# AND_opertaions.net
KiCad netlist of a schematic drawn in Altium Designer
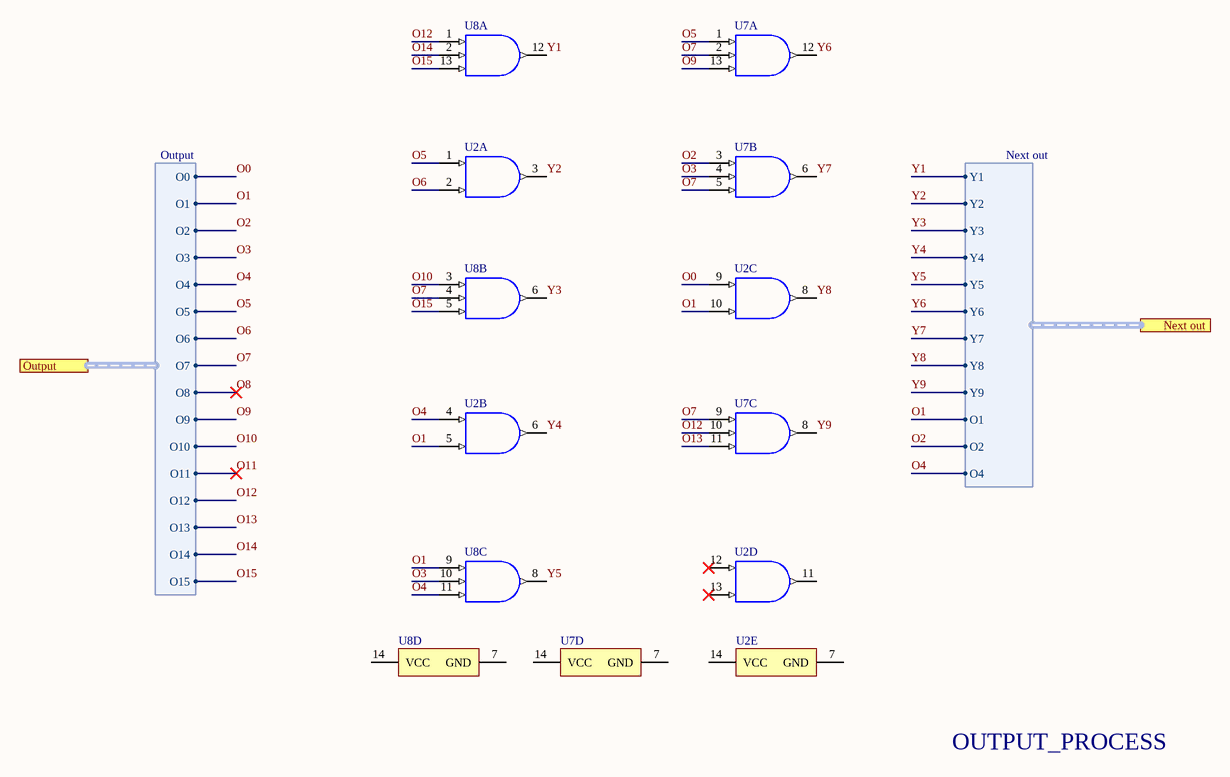
[diagram p0: AND_opertaions.SchDoc]

(export (version "E")
  (design (tool "Eeschema 10.0.6"))
  (components
    (comp (ref "U2")
      (value "SN74S08N")
      (footprint "N0014A")
      (description "Quad 2-input positive-AND gates, N0014A, TUBE")
      (fields
        (field (name "MANUFACTURER") "Texas Instruments")
        (field (name "GENERIC PART NUMBER") "SN74S08")
      )
      (libsource (lib "Altium Content Vault") (part "TI-AND-4-2IN-14"))
    )
    (comp (ref "U7")
      (value "SN74LS11N")
      (footprint "N0014A")
      (description "Triple 3-input positive-AND gates, N0014A, TUBE")
      (fields
        (field (name "MANUFACTURER") "Texas Instruments")
        (field (name "GENERIC PART NUMBER") "SN74LS11")
      )
      (libsource (lib "Altium Content Vault") (part "TI-AND-3-3IN-14"))
    )
    (comp (ref "U8")
      (value "SN74LS11N")
      (footprint "N0014A")
      (description "Triple 3-input positive-AND gates, N0014A, TUBE")
      (fields
        (field (name "MANUFACTURER") "Texas Instruments")
        (field (name "GENERIC PART NUMBER") "SN74LS11")
      )
      (libsource (lib "Altium Content Vault") (part "TI-AND-3-3IN-14"))
    )
  )
  (nets
    (net (code "4") (name "/O0") (class "Default")
      (node (ref "U2") (pin "9") (pinfunction "3A_9") (pintype "input"))
    )
    (net (code "5") (name "/O1") (class "Default")
      (node (ref "U2") (pin "10") (pinfunction "3B_10") (pintype "input"))
      (node (ref "U2") (pin "5") (pinfunction "2B_5") (pintype "input"))
      (node (ref "U8") (pin "9") (pinfunction "3A_9") (pintype "input"))
    )
    (net (code "6") (name "/O2") (class "Default")
      (node (ref "U7") (pin "3") (pinfunction "2A_3") (pintype "input"))
    )
    (net (code "7") (name "/O3") (class "Default")
      (node (ref "U7") (pin "4") (pinfunction "2B_4") (pintype "input"))
      (node (ref "U8") (pin "10") (pinfunction "3B_10") (pintype "input"))
    )
    (net (code "8") (name "/O4") (class "Default")
      (node (ref "U2") (pin "4") (pinfunction "2A_4") (pintype "input"))
      (node (ref "U8") (pin "11") (pinfunction "3C_11") (pintype "input"))
    )
    (net (code "9") (name "/O5") (class "Default")
      (node (ref "U2") (pin "1") (pinfunction "1A_1") (pintype "input"))
      (node (ref "U7") (pin "1") (pinfunction "1A_1") (pintype "input"))
    )
    (net (code "10") (name "/O6") (class "Default")
      (node (ref "U2") (pin "2") (pinfunction "1B_2") (pintype "input"))
    )
    (net (code "11") (name "/O7") (class "Default")
      (node (ref "U7") (pin "2") (pinfunction "1B_2") (pintype "input"))
      (node (ref "U7") (pin "5") (pinfunction "2C_5") (pintype "input"))
      (node (ref "U7") (pin "9") (pinfunction "3A_9") (pintype "input"))
      (node (ref "U8") (pin "4") (pinfunction "2B_4") (pintype "input"))
    )
    (net (code "13") (name "/O9") (class "Default")
      (node (ref "U7") (pin "13") (pinfunction "1C_13") (pintype "input"))
    )
    (net (code "14") (name "/O10") (class "Default")
      (node (ref "U8") (pin "3") (pinfunction "2A_3") (pintype "input"))
    )
    (net (code "16") (name "/O12") (class "Default")
      (node (ref "U7") (pin "10") (pinfunction "3B_10") (pintype "input"))
      (node (ref "U8") (pin "1") (pinfunction "1A_1") (pintype "input"))
    )
    (net (code "17") (name "/O13") (class "Default")
      (node (ref "U7") (pin "11") (pinfunction "3C_11") (pintype "input"))
    )
    (net (code "18") (name "/O14") (class "Default")
      (node (ref "U8") (pin "2") (pinfunction "1B_2") (pintype "input"))
    )
    (net (code "19") (name "/O15") (class "Default")
      (node (ref "U8") (pin "13") (pinfunction "1C_13") (pintype "input"))
      (node (ref "U8") (pin "5") (pinfunction "2C_5") (pintype "input"))
    )
    (net (code "20") (name "/Y1") (class "Default")
      (node (ref "U8") (pin "12") (pinfunction "1Y_12") (pintype "output"))
    )
    (net (code "21") (name "/Y2") (class "Default")
      (node (ref "U2") (pin "3") (pinfunction "1Y_3") (pintype "output"))
    )
    (net (code "22") (name "/Y3") (class "Default")
      (node (ref "U8") (pin "6") (pinfunction "2Y_6") (pintype "output"))
    )
    (net (code "23") (name "/Y4") (class "Default")
      (node (ref "U2") (pin "6") (pinfunction "2Y_6") (pintype "output"))
    )
    (net (code "24") (name "/Y5") (class "Default")
      (node (ref "U8") (pin "8") (pinfunction "3Y_8") (pintype "output"))
    )
    (net (code "25") (name "/Y6") (class "Default")
      (node (ref "U7") (pin "12") (pinfunction "1Y_12") (pintype "output"))
    )
    (net (code "26") (name "/Y7") (class "Default")
      (node (ref "U7") (pin "6") (pinfunction "2Y_6") (pintype "output"))
    )
    (net (code "27") (name "/Y8") (class "Default")
      (node (ref "U2") (pin "8") (pinfunction "3Y_8") (pintype "output"))
    )
    (net (code "28") (name "/Y9") (class "Default")
      (node (ref "U7") (pin "8") (pinfunction "3Y_8") (pintype "output"))
    )
    (net (code "31") (name "unconnected-(U2D-4A-Pad12)") (class "Default")
      (node (ref "U2") (pin "12") (pinfunction "4A_12") (pintype "input+no_connect"))
    )
    (net (code "32") (name "unconnected-(U2D-4B-Pad13)") (class "Default")
      (node (ref "U2") (pin "13") (pinfunction "4B_13") (pintype "input+no_connect"))
    )
    (net (code "33") (name "unconnected-(U2D-4Y-Pad11)") (class "Default")
      (node (ref "U2") (pin "11") (pinfunction "4Y_11") (pintype "output"))
    )
    (net (code "34") (name "unconnected-(U2E-GND-Pad7)") (class "Default")
      (node (ref "U2") (pin "7") (pinfunction "GND_7") (pintype "power_in"))
    )
    (net (code "35") (name "unconnected-(U2E-VCC-Pad14)") (class "Default")
      (node (ref "U2") (pin "14") (pinfunction "VCC_14") (pintype "power_in"))
    )
    (net (code "36") (name "unconnected-(U7D-GND-Pad7)") (class "Default")
      (node (ref "U7") (pin "7") (pinfunction "GND_7") (pintype "power_in"))
    )
    (net (code "37") (name "unconnected-(U7D-VCC-Pad14)") (class "Default")
      (node (ref "U7") (pin "14") (pinfunction "VCC_14") (pintype "power_in"))
    )
    (net (code "38") (name "unconnected-(U8D-GND-Pad7)") (class "Default")
      (node (ref "U8") (pin "7") (pinfunction "GND_7") (pintype "power_in"))
    )
    (net (code "39") (name "unconnected-(U8D-VCC-Pad14)") (class "Default")
      (node (ref "U8") (pin "14") (pinfunction "VCC_14") (pintype "power_in"))
    )
  )
)
